# CCM_0020_two_channel_translator.net
KiCad netlist of a schematic drawn in EAGLE
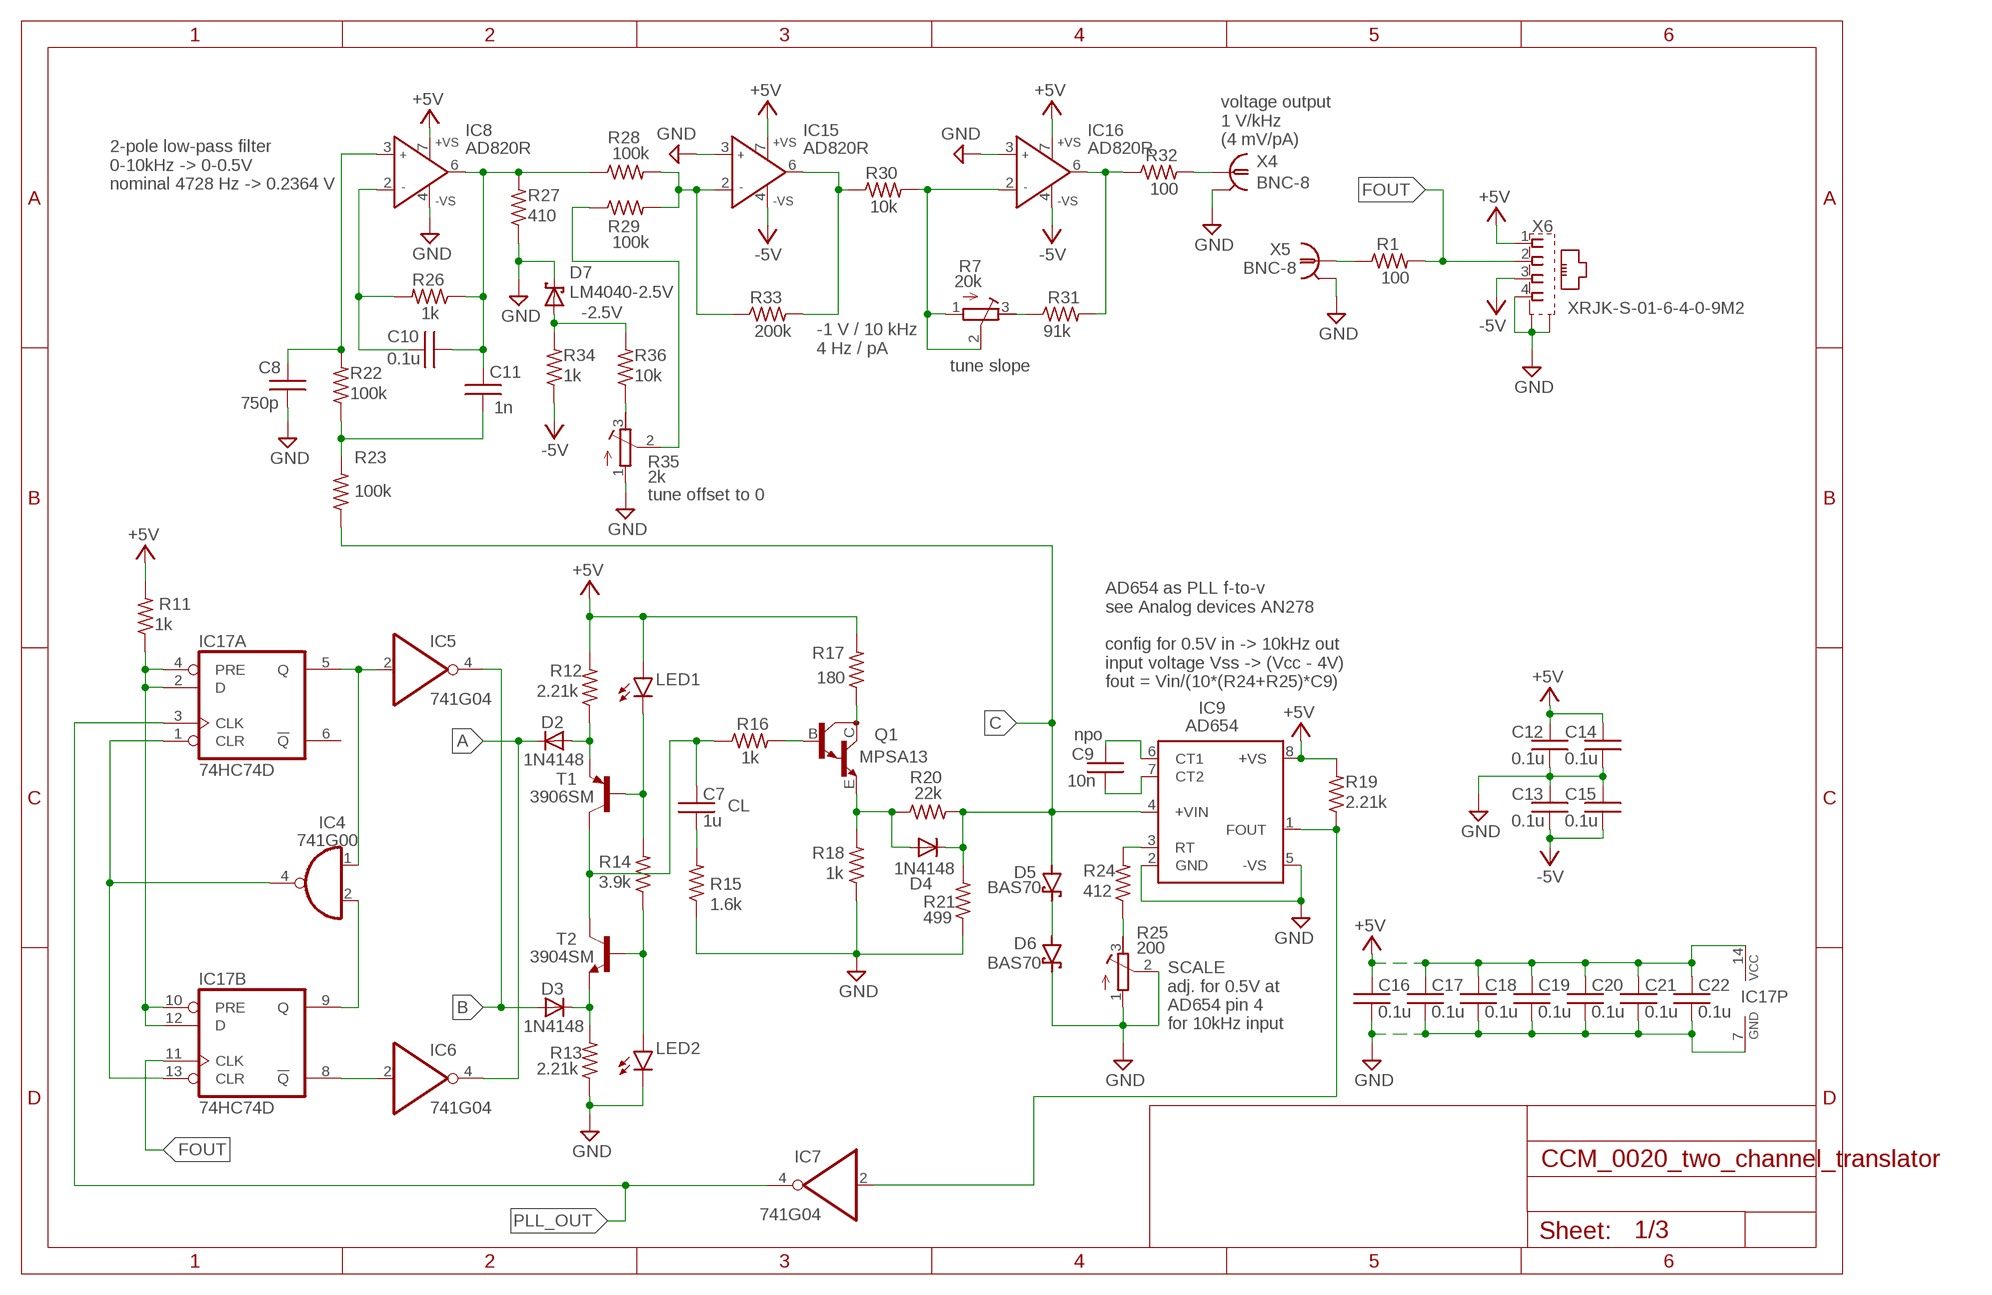
[diagram p0: schematic, sheet 1]
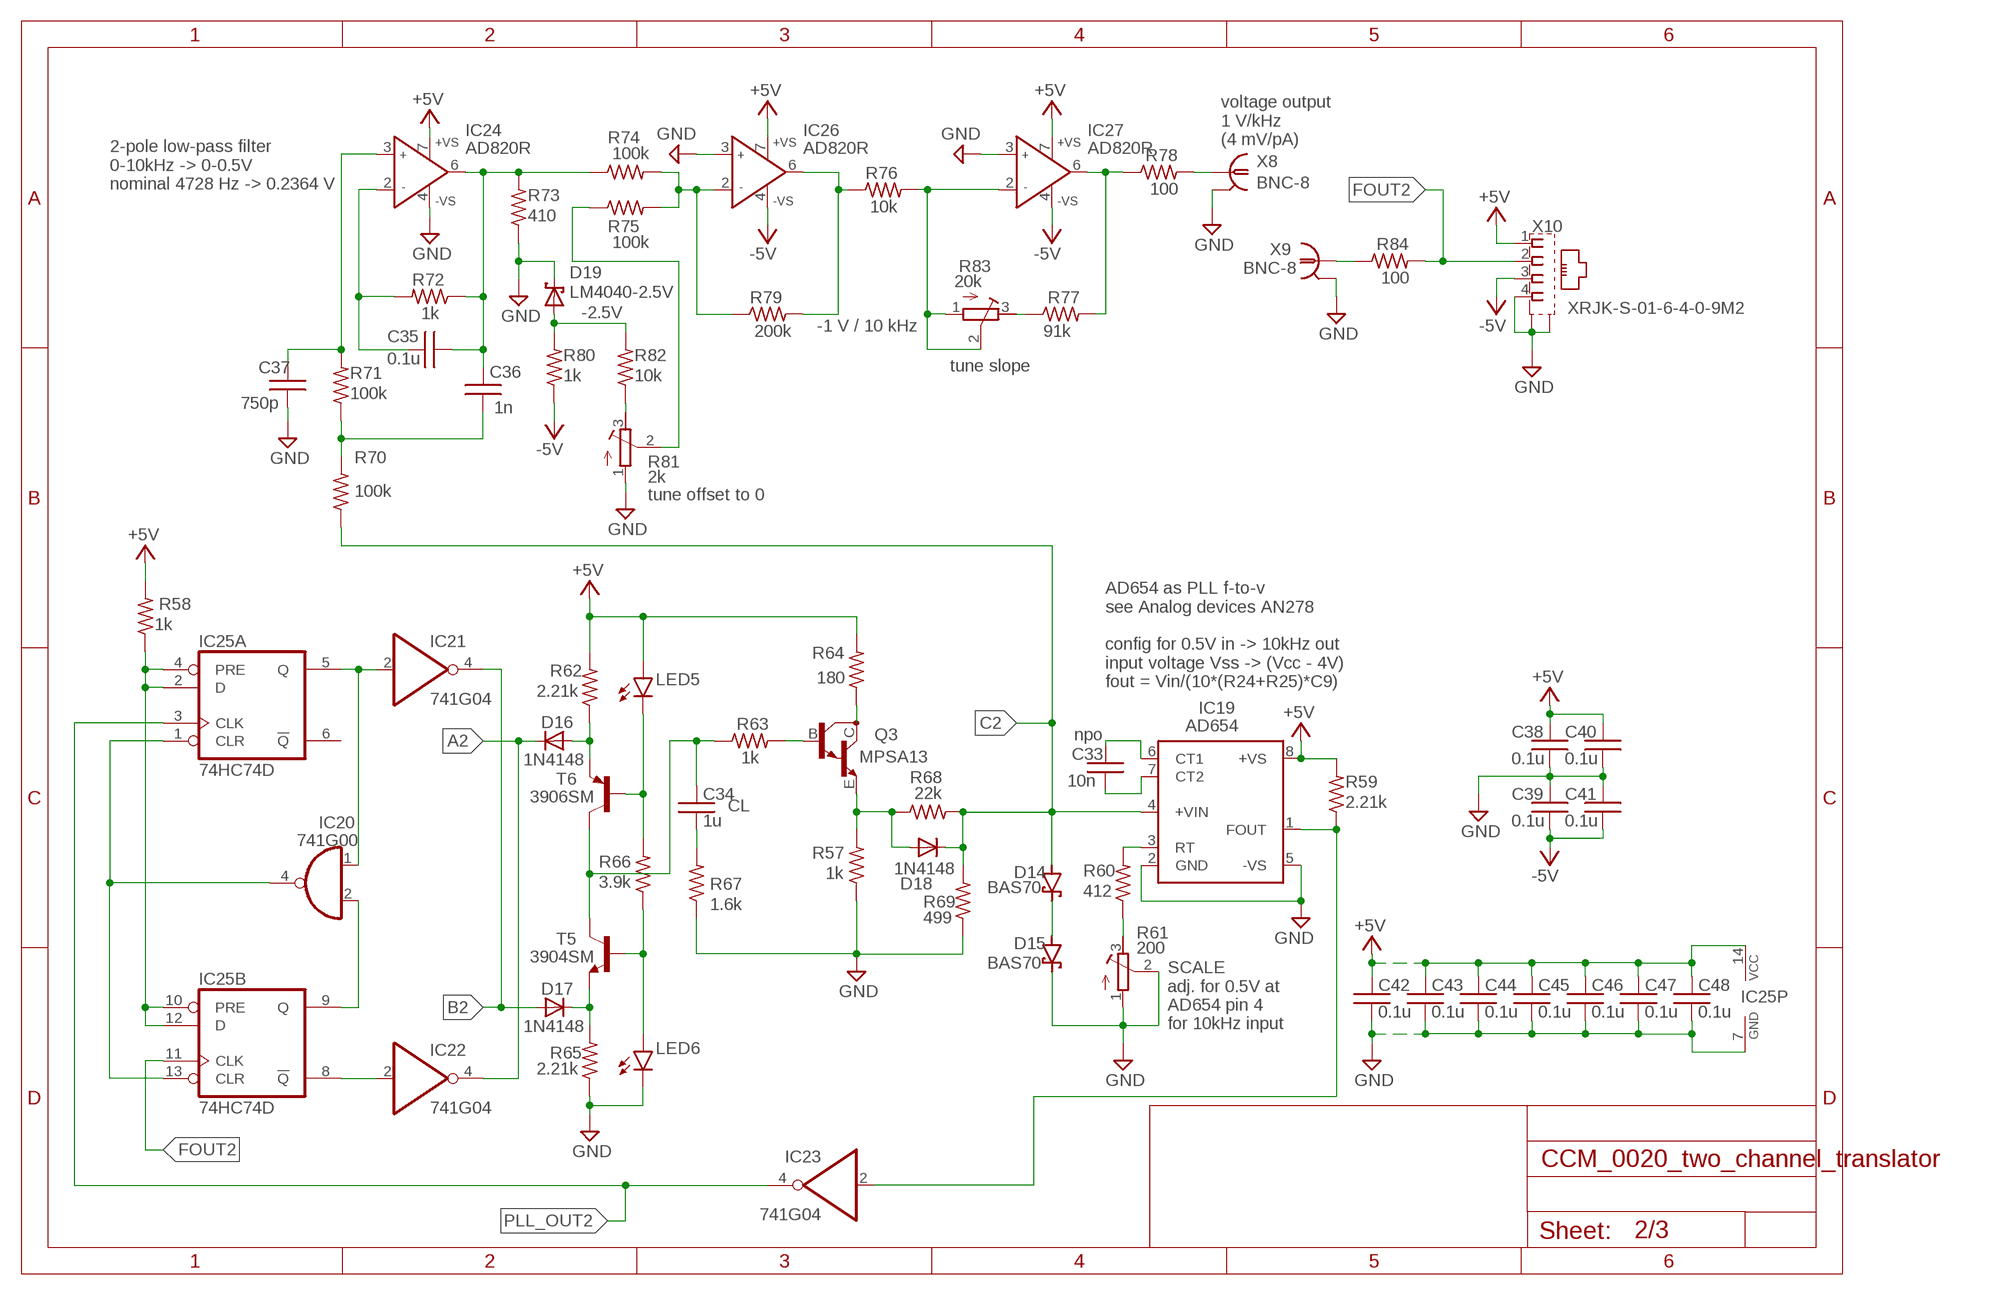
[diagram p1: schematic, sheet 2]
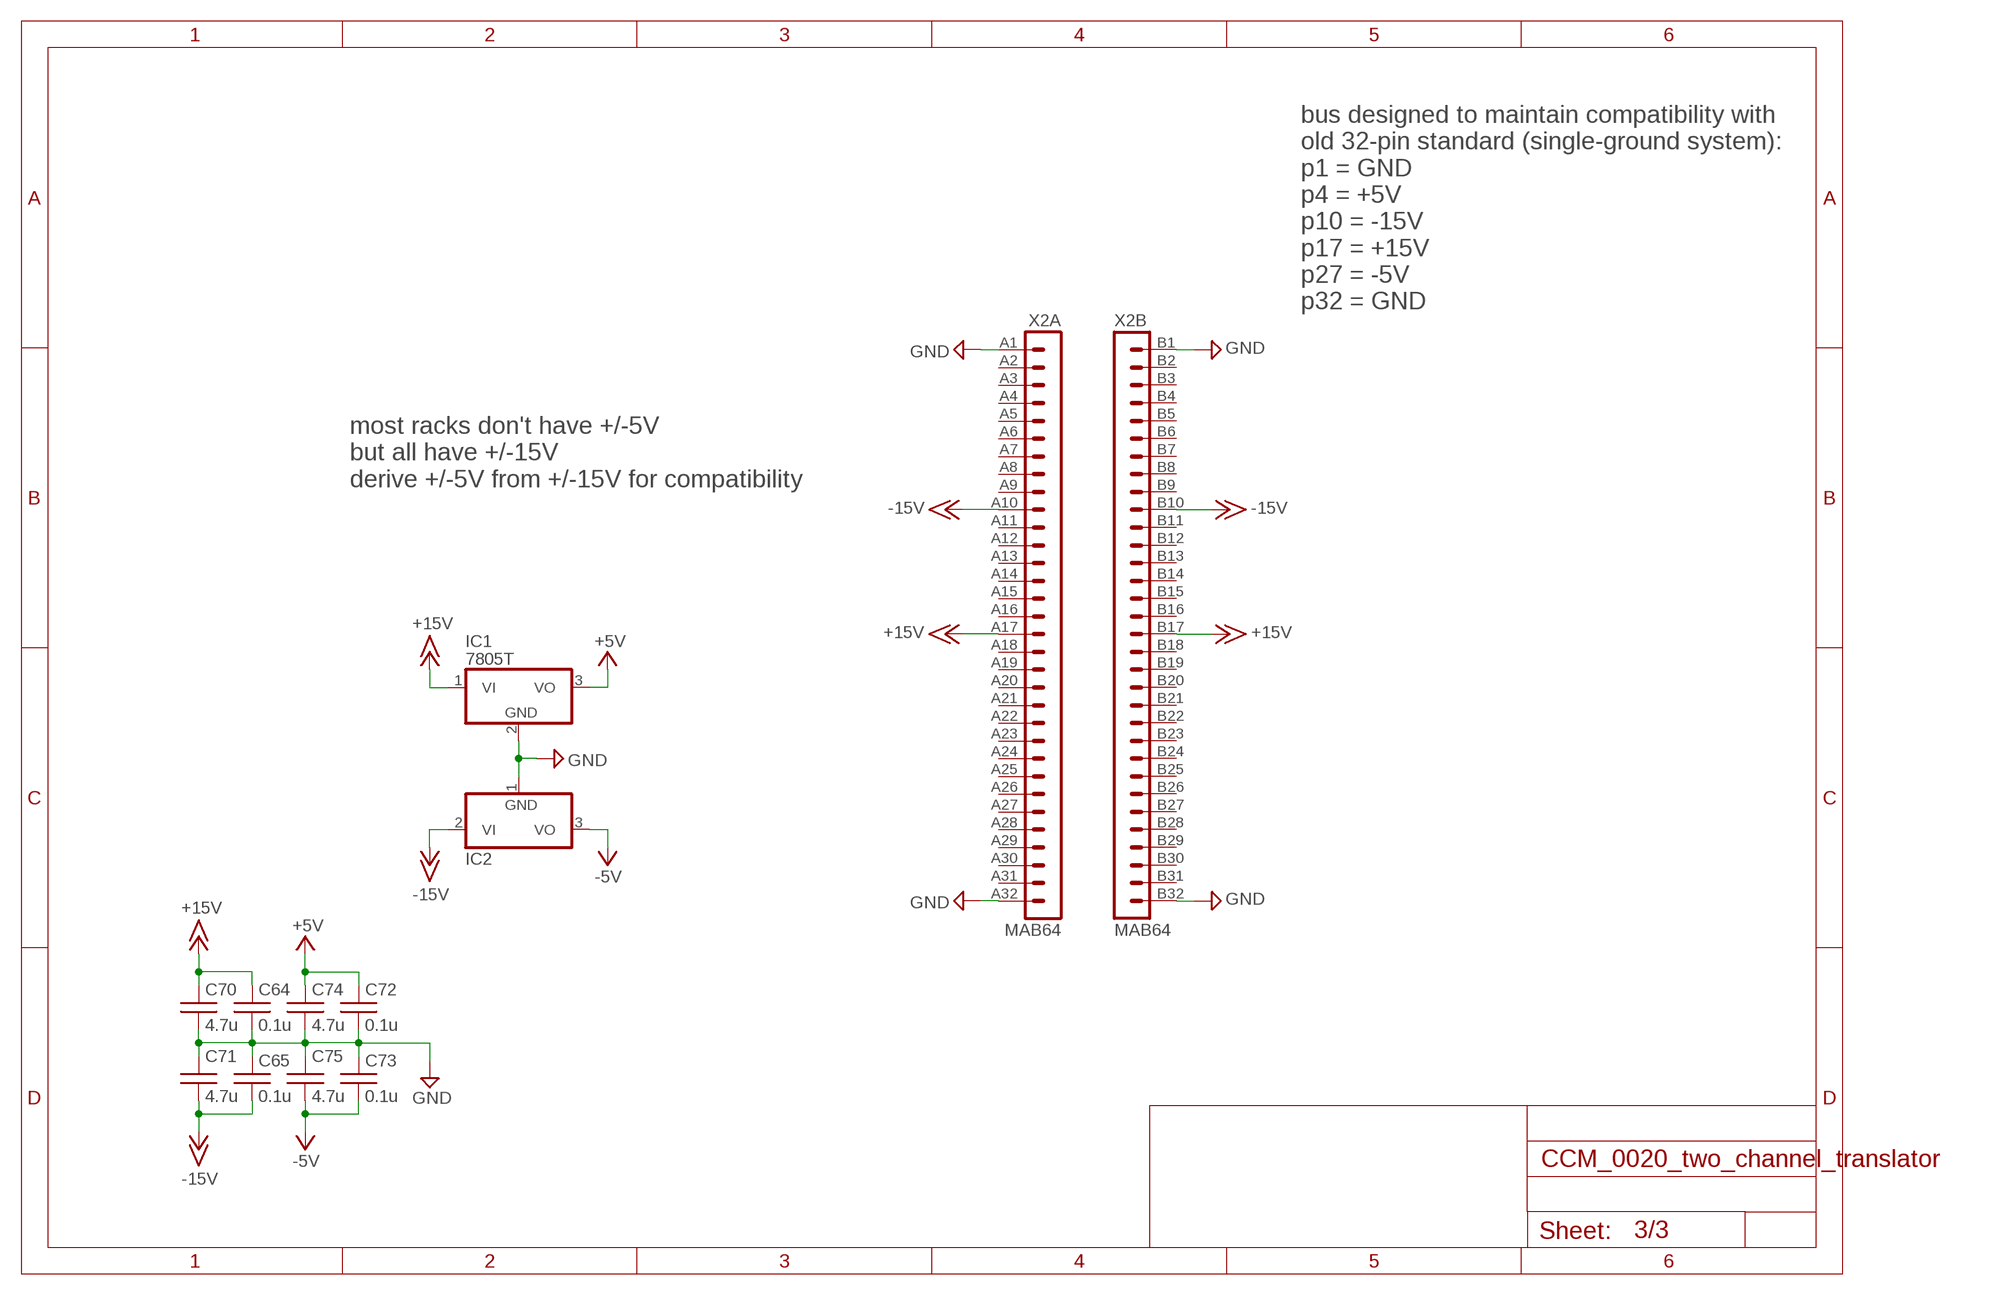
[diagram p2: schematic, sheet 3]

(export (version "E")
  (design (tool "Eeschema 10.0.6"))
  (components
    (comp (ref "C64")
      (value "0.1u")
      (footprint "eagle-import:0603")
      (libsource (lib "eagle-import") (part "C0603"))
    )
    (comp (ref "C65")
      (value "0.1u")
      (footprint "eagle-import:0603")
      (libsource (lib "eagle-import") (part "C0603"))
    )
    (comp (ref "C70")
      (value "4.7u")
      (footprint "eagle-import:0603")
      (libsource (lib "eagle-import") (part "C0603"))
    )
    (comp (ref "C71")
      (value "4.7u")
      (footprint "eagle-import:0603")
      (libsource (lib "eagle-import") (part "C0603"))
    )
    (comp (ref "C72")
      (value "0.1u")
      (footprint "eagle-import:0603")
      (libsource (lib "eagle-import") (part "C0603"))
    )
    (comp (ref "C73")
      (value "0.1u")
      (footprint "eagle-import:0603")
      (libsource (lib "eagle-import") (part "C0603"))
    )
    (comp (ref "C74")
      (value "4.7u")
      (footprint "eagle-import:0603")
      (libsource (lib "eagle-import") (part "C0603"))
    )
    (comp (ref "C75")
      (value "4.7u")
      (footprint "eagle-import:0603")
      (libsource (lib "eagle-import") (part "C0603"))
    )
    (comp (ref "IC1")
      (value "7805T")
      (footprint "eagle-import:TO220H")
      (libsource (lib "eagle-import") (part "78T05"))
    )
    (comp (ref "IC2")
      (value "7905T")
      (footprint "eagle-import:TO220H")
      (libsource (lib "eagle-import") (part "79T05"))
    )
    (comp (ref "X2")
      (value "MAB64")
      (footprint "eagle-import:MAB64")
      (libsource (lib "eagle-import") (part "MAB64"))
    )
    (comp (ref "C7")
      (value "1u")
      (footprint "eagle-import:0603")
      (libsource (lib "eagle-import") (part "C0603"))
    )
    (comp (ref "C8")
      (value "750p")
      (footprint "eagle-import:0603")
      (libsource (lib "eagle-import") (part "C0603"))
    )
    (comp (ref "C9")
      (value "10n")
      (footprint "eagle-import:0603")
      (libsource (lib "eagle-import") (part "C0603"))
    )
    (comp (ref "C10")
      (value "0.1u")
      (footprint "eagle-import:0603")
      (libsource (lib "eagle-import") (part "C0603"))
    )
    (comp (ref "C11")
      (value "1n")
      (footprint "eagle-import:0603")
      (libsource (lib "eagle-import") (part "C0603"))
    )
    (comp (ref "C12")
      (value "0.1u")
      (footprint "eagle-import:0603")
      (libsource (lib "eagle-import") (part "C0603"))
    )
    (comp (ref "C13")
      (value "0.1u")
      (footprint "eagle-import:0603")
      (libsource (lib "eagle-import") (part "C0603"))
    )
    (comp (ref "C14")
      (value "0.1u")
      (footprint "eagle-import:0603")
      (libsource (lib "eagle-import") (part "C0603"))
    )
    (comp (ref "C15")
      (value "0.1u")
      (footprint "eagle-import:0603")
      (libsource (lib "eagle-import") (part "C0603"))
    )
    (comp (ref "C16")
      (value "0.1u")
      (footprint "eagle-import:0603")
      (libsource (lib "eagle-import") (part "C0603"))
    )
    (comp (ref "C17")
      (value "0.1u")
      (footprint "eagle-import:0603")
      (libsource (lib "eagle-import") (part "C0603"))
    )
    (comp (ref "C18")
      (value "0.1u")
      (footprint "eagle-import:0603")
      (libsource (lib "eagle-import") (part "C0603"))
    )
    (comp (ref "C19")
      (value "0.1u")
      (footprint "eagle-import:0603")
      (libsource (lib "eagle-import") (part "C0603"))
    )
    (comp (ref "C20")
      (value "0.1u")
      (footprint "eagle-import:0603")
      (libsource (lib "eagle-import") (part "C0603"))
    )
    (comp (ref "C21")
      (value "0.1u")
      (footprint "eagle-import:0603")
      (libsource (lib "eagle-import") (part "C0603"))
    )
    (comp (ref "C22")
      (value "0.1u")
      (footprint "eagle-import:0603")
      (libsource (lib "eagle-import") (part "C0603"))
    )
    (comp (ref "D2")
      (value "1N4148")
      (footprint "eagle-import:SOD323_ST")
      (libsource (lib "eagle-import") (part "1N4148"))
    )
    (comp (ref "D3")
      (value "1N4148")
      (footprint "eagle-import:SOD323_ST")
      (libsource (lib "eagle-import") (part "1N4148"))
    )
    (comp (ref "D4")
      (value "1N4148")
      (footprint "eagle-import:SOD323_ST")
      (libsource (lib "eagle-import") (part "1N4148"))
    )
    (comp (ref "D5")
      (value "BAS70")
      (footprint "eagle-import:SOT23")
      (libsource (lib "eagle-import") (part "BAS70"))
    )
    (comp (ref "D6")
      (value "BAS70")
      (footprint "eagle-import:SOT23")
      (libsource (lib "eagle-import") (part "BAS70"))
    )
    (comp (ref "D7")
      (value "LM4040-2.5V")
      (footprint "eagle-import:SOT23")
      (libsource (lib "eagle-import") (part "LM4040"))
    )
    (comp (ref "IC4")
      (value "741G00")
      (footprint "eagle-import:SOT23-5")
      (libsource (lib "eagle-import") (part "741G00DBVAHC"))
    )
    (comp (ref "IC5")
      (value "741G04")
      (footprint "eagle-import:SOT23-5")
      (libsource (lib "eagle-import") (part "741G04DBVAHC"))
    )
    (comp (ref "IC6")
      (value "741G04")
      (footprint "eagle-import:SOT23-5")
      (libsource (lib "eagle-import") (part "741G04DBVAHC"))
    )
    (comp (ref "IC7")
      (value "741G04")
      (footprint "eagle-import:SOT23-5")
      (libsource (lib "eagle-import") (part "741G04DBVAHC"))
    )
    (comp (ref "IC8")
      (value "AD820R")
      (footprint "eagle-import:SO8")
      (libsource (lib "eagle-import") (part "AD820R"))
    )
    (comp (ref "IC9")
      (value "AD654")
      (footprint "eagle-import:SO08")
      (libsource (lib "eagle-import") (part "AD654"))
    )
    (comp (ref "IC15")
      (value "AD820R")
      (footprint "eagle-import:SO8")
      (libsource (lib "eagle-import") (part "AD820R"))
    )
    (comp (ref "IC16")
      (value "AD820R")
      (footprint "eagle-import:SO8")
      (libsource (lib "eagle-import") (part "AD820R"))
    )
    (comp (ref "IC17")
      (value "74HC74D")
      (footprint "eagle-import:SO14")
      (libsource (lib "eagle-import") (part "7474DHC"))
    )
    (comp (ref "LED1")
      (value "LEDCHIP-LED0603")
      (footprint "eagle-import:CHIP-LED0603")
      (libsource (lib "eagle-import") (part "LEDCHIP-LED0603"))
    )
    (comp (ref "LED2")
      (value "LEDCHIP-LED0603")
      (footprint "eagle-import:CHIP-LED0603")
      (libsource (lib "eagle-import") (part "LEDCHIP-LED0603"))
    )
    (comp (ref "Q1")
      (value "MPSA13")
      (footprint "eagle-import:SOT23-BEC")
      (libsource (lib "eagle-import") (part "MMBTA13LT1"))
    )
    (comp (ref "R1")
      (value "100")
      (footprint "eagle-import:0603")
      (libsource (lib "eagle-import") (part "R0603"))
    )
    (comp (ref "R7")
      (value "20k")
      (footprint "eagle-import:RTRIM64Y")
      (libsource (lib "eagle-import") (part "R-TRIMM64Y"))
    )
    (comp (ref "R11")
      (value "1k")
      (footprint "eagle-import:0603")
      (libsource (lib "eagle-import") (part "R0603"))
    )
    (comp (ref "R12")
      (value "2.21k")
      (footprint "eagle-import:0603")
      (libsource (lib "eagle-import") (part "R0603"))
    )
    (comp (ref "R13")
      (value "2.21k")
      (footprint "eagle-import:0603")
      (libsource (lib "eagle-import") (part "R0603"))
    )
    (comp (ref "R14")
      (value "3.9k")
      (footprint "eagle-import:0603")
      (libsource (lib "eagle-import") (part "R0603"))
    )
    (comp (ref "R15")
      (value "1.6k")
      (footprint "eagle-import:0603")
      (libsource (lib "eagle-import") (part "R0603"))
    )
    (comp (ref "R16")
      (value "1k")
      (footprint "eagle-import:0603")
      (libsource (lib "eagle-import") (part "R0603"))
    )
    (comp (ref "R17")
      (value "180")
      (footprint "eagle-import:0603")
      (libsource (lib "eagle-import") (part "R0603"))
    )
    (comp (ref "R18")
      (value "1k")
      (footprint "eagle-import:0603")
      (libsource (lib "eagle-import") (part "R0603"))
    )
    (comp (ref "R19")
      (value "2.21k")
      (footprint "eagle-import:0603")
      (libsource (lib "eagle-import") (part "R0603"))
    )
    (comp (ref "R20")
      (value "22k")
      (footprint "eagle-import:0603")
      (libsource (lib "eagle-import") (part "R0603"))
    )
    (comp (ref "R21")
      (value "499")
      (footprint "eagle-import:0603")
      (libsource (lib "eagle-import") (part "R0603"))
    )
    (comp (ref "R22")
      (value "100k")
      (footprint "eagle-import:0603")
      (libsource (lib "eagle-import") (part "R0603"))
    )
    (comp (ref "R23")
      (value "100k")
      (footprint "eagle-import:0603")
      (libsource (lib "eagle-import") (part "R0603"))
    )
    (comp (ref "R24")
      (value "412")
      (footprint "eagle-import:0603")
      (libsource (lib "eagle-import") (part "R0603"))
    )
    (comp (ref "R25")
      (value "200")
      (footprint "eagle-import:RTRIM64Y")
      (libsource (lib "eagle-import") (part "R-TRIMM64Y"))
    )
    (comp (ref "R26")
      (value "1k")
      (footprint "eagle-import:0603")
      (libsource (lib "eagle-import") (part "R0603"))
    )
    (comp (ref "R27")
      (value "410")
      (footprint "eagle-import:0603")
      (libsource (lib "eagle-import") (part "R0603"))
    )
    (comp (ref "R28")
      (value "100k")
      (footprint "eagle-import:0603")
      (libsource (lib "eagle-import") (part "R0603"))
    )
    (comp (ref "R29")
      (value "100k")
      (footprint "eagle-import:0603")
      (libsource (lib "eagle-import") (part "R0603"))
    )
    (comp (ref "R30")
      (value "10k")
      (footprint "eagle-import:0603")
      (libsource (lib "eagle-import") (part "R0603"))
    )
    (comp (ref "R31")
      (value "91k")
      (footprint "eagle-import:0603")
      (libsource (lib "eagle-import") (part "R0603"))
    )
    (comp (ref "R32")
      (value "100")
      (footprint "eagle-import:0603")
      (libsource (lib "eagle-import") (part "R0603"))
    )
    (comp (ref "R33")
      (value "200k")
      (footprint "eagle-import:0603")
      (libsource (lib "eagle-import") (part "R0603"))
    )
    (comp (ref "R34")
      (value "1k")
      (footprint "eagle-import:0603")
      (libsource (lib "eagle-import") (part "R0603"))
    )
    (comp (ref "R35")
      (value "2k")
      (footprint "eagle-import:RTRIM64Y")
      (libsource (lib "eagle-import") (part "R-TRIMM64Y"))
    )
    (comp (ref "R36")
      (value "10k")
      (footprint "eagle-import:0603")
      (libsource (lib "eagle-import") (part "R0603"))
    )
    (comp (ref "T1")
      (value "3906SM")
      (footprint "eagle-import:SOT23-BEC")
      (libsource (lib "eagle-import") (part "-PNP-SOT23-BECMMBT3906LT1"))
    )
    (comp (ref "T2")
      (value "3904SM")
      (footprint "eagle-import:SOT23")
      (libsource (lib "eagle-import") (part "3904SM"))
    )
    (comp (ref "X4")
      (value "BNC-8")
      (footprint "eagle-import:BNC_RA")
      (libsource (lib "eagle-import") (part "BNC-8"))
    )
    (comp (ref "X5")
      (value "BNC-8")
      (footprint "eagle-import:BNC_RA")
      (libsource (lib "eagle-import") (part "BNC-8"))
    )
    (comp (ref "X6")
      (value "XRJK-S-01-6-4-0-9M2")
      (footprint "eagle-import:XRJK-S-01-6-4-0-9M2")
      (libsource (lib "eagle-import") (part "XRJK4-0-9M2-S-01-6-"))
    )
    (comp (ref "C33")
      (value "10n")
      (footprint "eagle-import:0603")
      (libsource (lib "eagle-import") (part "C0603"))
    )
    (comp (ref "C34")
      (value "1u")
      (footprint "eagle-import:0603")
      (libsource (lib "eagle-import") (part "C0603"))
    )
    (comp (ref "C35")
      (value "0.1u")
      (footprint "eagle-import:0603")
      (libsource (lib "eagle-import") (part "C0603"))
    )
    (comp (ref "C36")
      (value "1n")
      (footprint "eagle-import:0603")
      (libsource (lib "eagle-import") (part "C0603"))
    )
    (comp (ref "C37")
      (value "750p")
      (footprint "eagle-import:0603")
      (libsource (lib "eagle-import") (part "C0603"))
    )
    (comp (ref "C38")
      (value "0.1u")
      (footprint "eagle-import:0603")
      (libsource (lib "eagle-import") (part "C0603"))
    )
    (comp (ref "C39")
      (value "0.1u")
      (footprint "eagle-import:0603")
      (libsource (lib "eagle-import") (part "C0603"))
    )
    (comp (ref "C40")
      (value "0.1u")
      (footprint "eagle-import:0603")
      (libsource (lib "eagle-import") (part "C0603"))
    )
    (comp (ref "C41")
      (value "0.1u")
      (footprint "eagle-import:0603")
      (libsource (lib "eagle-import") (part "C0603"))
    )
    (comp (ref "C42")
      (value "0.1u")
      (footprint "eagle-import:0603")
      (libsource (lib "eagle-import") (part "C0603"))
    )
    (comp (ref "C43")
      (value "0.1u")
      (footprint "eagle-import:0603")
      (libsource (lib "eagle-import") (part "C0603"))
    )
    (comp (ref "C44")
      (value "0.1u")
      (footprint "eagle-import:0603")
      (libsource (lib "eagle-import") (part "C0603"))
    )
    (comp (ref "C45")
      (value "0.1u")
      (footprint "eagle-import:0603")
      (libsource (lib "eagle-import") (part "C0603"))
    )
    (comp (ref "C46")
      (value "0.1u")
      (footprint "eagle-import:0603")
      (libsource (lib "eagle-import") (part "C0603"))
    )
    (comp (ref "C47")
      (value "0.1u")
      (footprint "eagle-import:0603")
      (libsource (lib "eagle-import") (part "C0603"))
    )
    (comp (ref "C48")
      (value "0.1u")
      (footprint "eagle-import:0603")
      (libsource (lib "eagle-import") (part "C0603"))
    )
    (comp (ref "D14")
      (value "BAS70")
      (footprint "eagle-import:SOT23")
      (libsource (lib "eagle-import") (part "BAS70"))
    )
    (comp (ref "D15")
      (value "BAS70")
      (footprint "eagle-import:SOT23")
      (libsource (lib "eagle-import") (part "BAS70"))
    )
    (comp (ref "D16")
      (value "1N4148")
      (footprint "eagle-import:SOD323_ST")
      (libsource (lib "eagle-import") (part "1N4148"))
    )
    (comp (ref "D17")
      (value "1N4148")
      (footprint "eagle-import:SOD323_ST")
      (libsource (lib "eagle-import") (part "1N4148"))
    )
    (comp (ref "D18")
      (value "1N4148")
      (footprint "eagle-import:SOD323_ST")
      (libsource (lib "eagle-import") (part "1N4148"))
    )
    (comp (ref "D19")
      (value "LM4040-2.5V")
      (footprint "eagle-import:SOT23")
      (libsource (lib "eagle-import") (part "LM4040"))
    )
    (comp (ref "IC19")
      (value "AD654")
      (footprint "eagle-import:SO08")
      (libsource (lib "eagle-import") (part "AD654"))
    )
    (comp (ref "IC20")
      (value "741G00")
      (footprint "eagle-import:SOT23-5")
      (libsource (lib "eagle-import") (part "741G00DBVAHC"))
    )
    (comp (ref "IC21")
      (value "741G04")
      (footprint "eagle-import:SOT23-5")
      (libsource (lib "eagle-import") (part "741G04DBVAHC"))
    )
    (comp (ref "IC22")
      (value "741G04")
      (footprint "eagle-import:SOT23-5")
      (libsource (lib "eagle-import") (part "741G04DBVAHC"))
    )
    (comp (ref "IC23")
      (value "741G04")
      (footprint "eagle-import:SOT23-5")
      (libsource (lib "eagle-import") (part "741G04DBVAHC"))
    )
    (comp (ref "IC24")
      (value "AD820R")
      (footprint "eagle-import:SO8")
      (libsource (lib "eagle-import") (part "AD820R"))
    )
    (comp (ref "IC25")
      (value "74HC74D")
      (footprint "eagle-import:SO14")
      (libsource (lib "eagle-import") (part "7474DHC"))
    )
    (comp (ref "IC26")
      (value "AD820R")
      (footprint "eagle-import:SO8")
      (libsource (lib "eagle-import") (part "AD820R"))
    )
    (comp (ref "IC27")
      (value "AD820R")
      (footprint "eagle-import:SO8")
      (libsource (lib "eagle-import") (part "AD820R"))
    )
    (comp (ref "LED5")
      (value "LEDCHIP-LED0603")
      (footprint "eagle-import:CHIP-LED0603")
      (libsource (lib "eagle-import") (part "LEDCHIP-LED0603"))
    )
    (comp (ref "LED6")
      (value "LEDCHIP-LED0603")
      (footprint "eagle-import:CHIP-LED0603")
      (libsource (lib "eagle-import") (part "LEDCHIP-LED0603"))
    )
    (comp (ref "Q3")
      (value "MPSA13")
      (footprint "eagle-import:SOT23-BEC")
      (libsource (lib "eagle-import") (part "MMBTA13LT1"))
    )
    (comp (ref "R57")
      (value "1k")
      (footprint "eagle-import:0603")
      (libsource (lib "eagle-import") (part "R0603"))
    )
    (comp (ref "R58")
      (value "1k")
      (footprint "eagle-import:0603")
      (libsource (lib "eagle-import") (part "R0603"))
    )
    (comp (ref "R59")
      (value "2.21k")
      (footprint "eagle-import:0603")
      (libsource (lib "eagle-import") (part "R0603"))
    )
    (comp (ref "R60")
      (value "412")
      (footprint "eagle-import:0603")
      (libsource (lib "eagle-import") (part "R0603"))
    )
    (comp (ref "R61")
      (value "200")
      (footprint "eagle-import:RTRIM64Y")
      (libsource (lib "eagle-import") (part "R-TRIMM64Y"))
    )
    (comp (ref "R62")
      (value "2.21k")
      (footprint "eagle-import:0603")
      (libsource (lib "eagle-import") (part "R0603"))
    )
    (comp (ref "R63")
      (value "1k")
      (footprint "eagle-import:0603")
      (libsource (lib "eagle-import") (part "R0603"))
    )
    (comp (ref "R64")
      (value "180")
      (footprint "eagle-import:0603")
      (libsource (lib "eagle-import") (part "R0603"))
    )
    (comp (ref "R65")
      (value "2.21k")
      (footprint "eagle-import:0603")
      (libsource (lib "eagle-import") (part "R0603"))
    )
    (comp (ref "R66")
      (value "3.9k")
      (footprint "eagle-import:0603")
      (libsource (lib "eagle-import") (part "R0603"))
    )
    (comp (ref "R67")
      (value "1.6k")
      (footprint "eagle-import:0603")
      (libsource (lib "eagle-import") (part "R0603"))
    )
    (comp (ref "R68")
      (value "22k")
      (footprint "eagle-import:0603")
      (libsource (lib "eagle-import") (part "R0603"))
    )
    (comp (ref "R69")
      (value "499")
      (footprint "eagle-import:0603")
      (libsource (lib "eagle-import") (part "R0603"))
    )
    (comp (ref "R70")
      (value "100k")
      (footprint "eagle-import:0603")
      (libsource (lib "eagle-import") (part "R0603"))
    )
    (comp (ref "R71")
      (value "100k")
      (footprint "eagle-import:0603")
      (libsource (lib "eagle-import") (part "R0603"))
    )
    (comp (ref "R72")
      (value "1k")
      (footprint "eagle-import:0603")
      (libsource (lib "eagle-import") (part "R0603"))
    )
    (comp (ref "R73")
      (value "410")
      (footprint "eagle-import:0603")
      (libsource (lib "eagle-import") (part "R0603"))
    )
    (comp (ref "R74")
      (value "100k")
      (footprint "eagle-import:0603")
      (libsource (lib "eagle-import") (part "R0603"))
    )
    (comp (ref "R75")
      (value "100k")
      (footprint "eagle-import:0603")
      (libsource (lib "eagle-import") (part "R0603"))
    )
    (comp (ref "R76")
      (value "10k")
      (footprint "eagle-import:0603")
      (libsource (lib "eagle-import") (part "R0603"))
    )
    (comp (ref "R77")
      (value "91k")
      (footprint "eagle-import:0603")
      (libsource (lib "eagle-import") (part "R0603"))
    )
    (comp (ref "R78")
      (value "100")
      (footprint "eagle-import:0603")
      (libsource (lib "eagle-import") (part "R0603"))
    )
    (comp (ref "R79")
      (value "200k")
      (footprint "eagle-import:0603")
      (libsource (lib "eagle-import") (part "R0603"))
    )
    (comp (ref "R80")
      (value "1k")
      (footprint "eagle-import:0603")
      (libsource (lib "eagle-import") (part "R0603"))
    )
    (comp (ref "R81")
      (value "2k")
      (footprint "eagle-import:RTRIM64Y")
      (libsource (lib "eagle-import") (part "R-TRIMM64Y"))
    )
    (comp (ref "R82")
      (value "10k")
      (footprint "eagle-import:0603")
      (libsource (lib "eagle-import") (part "R0603"))
    )
    (comp (ref "R83")
      (value "20k")
      (footprint "eagle-import:RTRIM64Y")
      (libsource (lib "eagle-import") (part "R-TRIMM64Y"))
    )
    (comp (ref "R84")
      (value "100")
      (footprint "eagle-import:0603")
      (libsource (lib "eagle-import") (part "R0603"))
    )
    (comp (ref "T5")
      (value "3904SM")
      (footprint "eagle-import:SOT23")
      (libsource (lib "eagle-import") (part "3904SM"))
    )
    (comp (ref "T6")
      (value "3906SM")
      (footprint "eagle-import:SOT23-BEC")
      (libsource (lib "eagle-import") (part "-PNP-SOT23-BECMMBT3906LT1"))
    )
    (comp (ref "X8")
      (value "BNC-8")
      (footprint "eagle-import:BNC_RA")
      (libsource (lib "eagle-import") (part "BNC-8"))
    )
    (comp (ref "X9")
      (value "BNC-8")
      (footprint "eagle-import:BNC_RA")
      (libsource (lib "eagle-import") (part "BNC-8"))
    )
    (comp (ref "X10")
      (value "XRJK-S-01-6-4-0-9M2")
      (footprint "eagle-import:XRJK-S-01-6-4-0-9M2")
      (libsource (lib "eagle-import") (part "XRJK4-0-9M2-S-01-6-"))
    )
  )
  (nets
    (net (code "1") (name "+5V") (class "Default")
      (node (ref "C12") (pin "2") (pinfunction "2_2") (pintype "passive"))
      (node (ref "C14") (pin "2") (pinfunction "2_2") (pintype "passive"))
      (node (ref "C16") (pin "1") (pinfunction "1_1") (pintype "passive"))
      (node (ref "C17") (pin "1") (pinfunction "1_1") (pintype "passive"))
      (node (ref "C18") (pin "1") (pinfunction "1_1") (pintype "passive"))
      (node (ref "C19") (pin "1") (pinfunction "1_1") (pintype "passive"))
      (node (ref "C20") (pin "1") (pinfunction "1_1") (pintype "passive"))
      (node (ref "C21") (pin "1") (pinfunction "1_1") (pintype "passive"))
      (node (ref "C22") (pin "1") (pinfunction "1_1") (pintype "passive"))
      (node (ref "C38") (pin "2") (pinfunction "2_2") (pintype "passive"))
      (node (ref "C40") (pin "2") (pinfunction "2_2") (pintype "passive"))
      (node (ref "C42") (pin "1") (pinfunction "1_1") (pintype "passive"))
      (node (ref "C43") (pin "1") (pinfunction "1_1") (pintype "passive"))
      (node (ref "C44") (pin "1") (pinfunction "1_1") (pintype "passive"))
      (node (ref "C45") (pin "1") (pinfunction "1_1") (pintype "passive"))
      (node (ref "C46") (pin "1") (pinfunction "1_1") (pintype "passive"))
      (node (ref "C47") (pin "1") (pinfunction "1_1") (pintype "passive"))
      (node (ref "C48") (pin "1") (pinfunction "1_1") (pintype "passive"))
      (node (ref "C72") (pin "1") (pinfunction "1_1") (pintype "passive"))
      (node (ref "C74") (pin "1") (pinfunction "1_1") (pintype "passive"))
      (node (ref "IC1") (pin "3") (pinfunction "VO_3") (pintype "passive"))
      (node (ref "IC15") (pin "7") (pinfunction "+VS_7") (pintype "input"))
      (node (ref "IC16") (pin "7") (pinfunction "+VS_7") (pintype "input"))
      (node (ref "IC17") (pin "14") (pinfunction "VCC_14") (pintype "power_in"))
      (node (ref "IC19") (pin "8") (pinfunction "+VS_8") (pintype "power_in"))
      (node (ref "IC24") (pin "7") (pinfunction "+VS_7") (pintype "input"))
      (node (ref "IC25") (pin "14") (pinfunction "VCC_14") (pintype "power_in"))
      (node (ref "IC26") (pin "7") (pinfunction "+VS_7") (pintype "input"))
      (node (ref "IC27") (pin "7") (pinfunction "+VS_7") (pintype "input"))
      (node (ref "IC8") (pin "7") (pinfunction "+VS_7") (pintype "input"))
      (node (ref "IC9") (pin "8") (pinfunction "+VS_8") (pintype "power_in"))
      (node (ref "LED1") (pin "A") (pinfunction "A_A") (pintype "passive"))
      (node (ref "LED5") (pin "A") (pinfunction "A_A") (pintype "passive"))
      (node (ref "R11") (pin "2") (pinfunction "2_2") (pintype "passive"))
      (node (ref "R12") (pin "2") (pinfunction "2_2") (pintype "passive"))
      (node (ref "R17") (pin "2") (pinfunction "2_2") (pintype "passive"))
      (node (ref "R19") (pin "2") (pinfunction "2_2") (pintype "passive"))
      (node (ref "R58") (pin "2") (pinfunction "2_2") (pintype "passive"))
      (node (ref "R59") (pin "2") (pinfunction "2_2") (pintype "passive"))
      (node (ref "R62") (pin "2") (pinfunction "2_2") (pintype "passive"))
      (node (ref "R64") (pin "2") (pinfunction "2_2") (pintype "passive"))
      (node (ref "X10") (pin "1") (pinfunction "1_1") (pintype "passive"))
      (node (ref "X6") (pin "1") (pinfunction "1_1") (pintype "passive"))
    )
    (net (code "2") (name "+15V") (class "Default")
      (node (ref "C64") (pin "1") (pinfunction "1_1") (pintype "passive"))
      (node (ref "C70") (pin "1") (pinfunction "1_1") (pintype "passive"))
      (node (ref "IC1") (pin "1") (pinfunction "VI_1") (pintype "input"))
      (node (ref "X2") (pin "A17") (pinfunction "17_A17") (pintype "passive"))
      (node (ref "X2") (pin "B17") (pinfunction "17_B17") (pintype "passive"))
    )
    (net (code "3") (name "-5V") (class "Default")
      (node (ref "C13") (pin "1") (pinfunction "1_1") (pintype "passive"))
      (node (ref "C15") (pin "1") (pinfunction "1_1") (pintype "passive"))
      (node (ref "C39") (pin "1") (pinfunction "1_1") (pintype "passive"))
      (node (ref "C41") (pin "1") (pinfunction "1_1") (pintype "passive"))
      (node (ref "C73") (pin "2") (pinfunction "2_2") (pintype "passive"))
      (node (ref "C75") (pin "2") (pinfunction "2_2") (pintype "passive"))
      (node (ref "IC15") (pin "4") (pinfunction "-VS_4") (pintype "input"))
      (node (ref "IC16") (pin "4") (pinfunction "-VS_4") (pintype "input"))
      (node (ref "IC2") (pin "3") (pinfunction "VO_3") (pintype "passive"))
      (node (ref "IC26") (pin "4") (pinfunction "-VS_4") (pintype "input"))
      (node (ref "IC27") (pin "4") (pinfunction "-VS_4") (pintype "input"))
      (node (ref "R34") (pin "1") (pinfunction "1_1") (pintype "passive"))
      (node (ref "R80") (pin "1") (pinfunction "1_1") (pintype "passive"))
      (node (ref "X10") (pin "3") (pinfunction "3_3") (pintype "passive"))
      (node (ref "X6") (pin "3") (pinfunction "3_3") (pintype "passive"))
    )
    (net (code "4") (name "-15V") (class "Default")
      (node (ref "C65") (pin "2") (pinfunction "2_2") (pintype "passive"))
      (node (ref "C71") (pin "2") (pinfunction "2_2") (pintype "passive"))
      (node (ref "IC2") (pin "2") (pinfunction "VI_2") (pintype "input"))
      (node (ref "X2") (pin "A10") (pinfunction "10_A10") (pintype "passive"))
      (node (ref "X2") (pin "B10") (pinfunction "10_B10") (pintype "passive"))
    )
    (net (code "5") (name "A") (class "Default")
      (node (ref "D2") (pin "C") (pinfunction "C_C") (pintype "passive"))
      (node (ref "IC6") (pin "4") (pinfunction "O_4") (pintype "output"))
    )
    (net (code "6") (name "A2") (class "Default")
      (node (ref "D16") (pin "C") (pinfunction "C_C") (pintype "passive"))
      (node (ref "IC22") (pin "4") (pinfunction "O_4") (pintype "output"))
    )
    (net (code "7") (name "B") (class "Default")
      (node (ref "D3") (pin "A") (pinfunction "A_A") (pintype "passive"))
      (node (ref "IC5") (pin "4") (pinfunction "O_4") (pintype "output"))
    )
    (net (code "8") (name "B2") (class "Default")
      (node (ref "D17") (pin "A") (pinfunction "A_A") (pintype "passive"))
      (node (ref "IC21") (pin "4") (pinfunction "O_4") (pintype "output"))
    )
    (net (code "9") (name "C") (class "Default")
      (node (ref "D4") (pin "C") (pinfunction "C_C") (pintype "passive"))
      (node (ref "D5") (pin "1") (pinfunction "A_1") (pintype "passive"))
      (node (ref "IC9") (pin "4") (pinfunction "+VIN_4") (pintype "input"))
      (node (ref "R20") (pin "2") (pinfunction "2_2") (pintype "passive"))
      (node (ref "R21") (pin "2") (pinfunction "2_2") (pintype "passive"))
      (node (ref "R23") (pin "1") (pinfunction "1_1") (pintype "passive"))
    )
    (net (code "10") (name "C2") (class "Default")
      (node (ref "D14") (pin "1") (pinfunction "A_1") (pintype "passive"))
      (node (ref "D18") (pin "C") (pinfunction "C_C") (pintype "passive"))
      (node (ref "IC19") (pin "4") (pinfunction "+VIN_4") (pintype "input"))
      (node (ref "R68") (pin "2") (pinfunction "2_2") (pintype "passive"))
      (node (ref "R69") (pin "2") (pinfunction "2_2") (pintype "passive"))
      (node (ref "R70") (pin "1") (pinfunction "1_1") (pintype "passive"))
    )
    (net (code "11") (name "FOUT") (class "Default")
      (node (ref "IC17") (pin "11") (pinfunction "CLK_11") (pintype "input"))
      (node (ref "R1") (pin "2") (pinfunction "2_2") (pintype "passive"))
      (node (ref "X6") (pin "2") (pinfunction "2_2") (pintype "passive"))
    )
    (net (code "12") (name "FOUT2") (class "Default")
      (node (ref "IC25") (pin "11") (pinfunction "CLK_11") (pintype "input"))
      (node (ref "R84") (pin "2") (pinfunction "2_2") (pintype "passive"))
      (node (ref "X10") (pin "2") (pinfunction "2_2") (pintype "passive"))
    )
    (net (code "13") (name "GND") (class "Default")
      (node (ref "C12") (pin "1") (pinfunction "1_1") (pintype "passive"))
      (node (ref "C13") (pin "2") (pinfunction "2_2") (pintype "passive"))
      (node (ref "C14") (pin "1") (pinfunction "1_1") (pintype "passive"))
      (node (ref "C15") (pin "2") (pinfunction "2_2") (pintype "passive"))
      (node (ref "C16") (pin "2") (pinfunction "2_2") (pintype "passive"))
      (node (ref "C17") (pin "2") (pinfunction "2_2") (pintype "passive"))
      (node (ref "C18") (pin "2") (pinfunction "2_2") (pintype "passive"))
      (node (ref "C19") (pin "2") (pinfunction "2_2") (pintype "passive"))
      (node (ref "C20") (pin "2") (pinfunction "2_2") (pintype "passive"))
      (node (ref "C21") (pin "2") (pinfunction "2_2") (pintype "passive"))
      (node (ref "C22") (pin "2") (pinfunction "2_2") (pintype "passive"))
      (node (ref "C37") (pin "1") (pinfunction "1_1") (pintype "passive"))
      (node (ref "C38") (pin "1") (pinfunction "1_1") (pintype "passive"))
      (node (ref "C39") (pin "2") (pinfunction "2_2") (pintype "passive"))
      (node (ref "C40") (pin "1") (pinfunction "1_1") (pintype "passive"))
      (node (ref "C41") (pin "2") (pinfunction "2_2") (pintype "passive"))
      (node (ref "C42") (pin "2") (pinfunction "2_2") (pintype "passive"))
      (node (ref "C43") (pin "2") (pinfunction "2_2") (pintype "passive"))
      (node (ref "C44") (pin "2") (pinfunction "2_2") (pintype "passive"))
      (node (ref "C45") (pin "2") (pinfunction "2_2") (pintype "passive"))
      (node (ref "C46") (pin "2") (pinfunction "2_2") (pintype "passive"))
      (node (ref "C47") (pin "2") (pinfunction "2_2") (pintype "passive"))
      (node (ref "C48") (pin "2") (pinfunction "2_2") (pintype "passive"))
      (node (ref "C64") (pin "2") (pinfunction "2_2") (pintype "passive"))
      (node (ref "C65") (pin "1") (pinfunction "1_1") (pintype "passive"))
      (node (ref "C70") (pin "2") (pinfunction "2_2") (pintype "passive"))
      (node (ref "C71") (pin "1") (pinfunction "1_1") (pintype "passive"))
      (node (ref "C72") (pin "2") (pinfunction "2_2") (pintype "passive"))
      (node (ref "C73") (pin "1") (pinfunction "1_1") (pintype "passive"))
      (node (ref "C74") (pin "2") (pinfunction "2_2") (pintype "passive"))
      (node (ref "C75") (pin "1") (pinfunction "1_1") (pintype "passive"))
      (node (ref "C8") (pin "1") (pinfunction "1_1") (pintype "passive"))
      (node (ref "D15") (pin "3") (pinfunction "C_3") (pintype "passive"))
      (node (ref "D19") (pin "1") (pinfunction "C_1") (pintype "passive"))
      (node (ref "D6") (pin "3") (pinfunction "C_3") (pintype "passive"))
      (node (ref "D7") (pin "1") (pinfunction "C_1") (pintype "passive"))
      (node (ref "IC1") (pin "2") (pinfunction "GND_2") (pintype "passive"))
      (node (ref "IC15") (pin "3") (pinfunction "IN+_3") (pintype "input"))
      (node (ref "IC16") (pin "3") (pinfunction "IN+_3") (pintype "input"))
      (node (ref "IC17") (pin "7") (pinfunction "GND_7") (pintype "power_in"))
      (node (ref "IC19") (pin "2") (pinfunction "GND_2") (pintype "power_in"))
      (node (ref "IC19") (pin "5") (pinfunction "-VS_5") (pintype "power_in"))
      (node (ref "IC2") (pin "1") (pinfunction "GND_1") (pintype "passive"))
      (node (ref "IC24") (pin "4") (pinfunction "-VS_4") (pintype "input"))
      (node (ref "IC25") (pin "7") (pinfunction "GND_7") (pintype "power_in"))
      (node (ref "IC26") (pin "3") (pinfunction "IN+_3") (pintype "input"))
      (node (ref "IC27") (pin "3") (pinfunction "IN+_3") (pintype "input"))
      (node (ref "IC8") (pin "4") (pinfunction "-VS_4") (pintype "input"))
      (node (ref "IC9") (pin "2") (pinfunction "GND_2") (pintype "power_in"))
      (node (ref "IC9") (pin "5") (pinfunction "-VS_5") (pintype "power_in"))
      (node (ref "LED2") (pin "C") (pinfunction "C_C") (pintype "passive"))
      (node (ref "LED6") (pin "C") (pinfunction "C_C") (pintype "passive"))
      (node (ref "R13") (pin "1") (pinfunction "1_1") (pintype "passive"))
      (node (ref "R15") (pin "1") (pinfunction "1_1") (pintype "passive"))
      (node (ref "R18") (pin "1") (pinfunction "1_1") (pintype "passive"))
      (node (ref "R21") (pin "1") (pinfunction "1_1") (pintype "passive"))
      (node (ref "R25") (pin "1") (pinfunction "A_1") (pintype "passive"))
      (node (ref "R25") (pin "2") (pinfunction "S_2") (pintype "passive"))
      (node (ref "R27") (pin "1") (pinfunction "1_1") (pintype "passive"))
      (node (ref "R35") (pin "1") (pinfunction "A_1") (pintype "passive"))
      (node (ref "R57") (pin "1") (pinfunction "1_1") (pintype "passive"))
      (node (ref "R61") (pin "1") (pinfunction "A_1") (pintype "passive"))
      (node (ref "R61") (pin "2") (pinfunction "S_2") (pintype "passive"))
      (node (ref "R65") (pin "1") (pinfunction "1_1") (pintype "passive"))
      (node (ref "R67") (pin "1") (pinfunction "1_1") (pintype "passive"))
      (node (ref "R69") (pin "1") (pinfunction "1_1") (pintype "passive"))
      (node (ref "R73") (pin "1") (pinfunction "1_1") (pintype "passive"))
      (node (ref "R81") (pin "1") (pinfunction "A_1") (pintype "passive"))
      (node (ref "X10") (pin "4") (pinfunction "4_4") (pintype "passive"))
      (node (ref "X10") (pin "S1") (pinfunction "S_S1") (pintype "passive"))
      (node (ref "X10") (pin "S2") (pinfunction "S_S2") (pintype "passive"))
      (node (ref "X2") (pin "A1") (pinfunction "1_A1") (pintype "passive"))
      (node (ref "X2") (pin "A32") (pinfunction "32_A32") (pintype "passive"))
      (node (ref "X2") (pin "B1") (pinfunction "1_B1") (pintype "passive"))
      (node (ref "X2") (pin "B32") (pinfunction "32_B32") (pintype "passive"))
      (node (ref "X4") (pin "2") (pinfunction "2_2") (pintype "passive"))
      (node (ref "X5") (pin "2") (pinfunction "2_2") (pintype "passive"))
      (node (ref "X6") (pin "4") (pinfunction "4_4") (pintype "passive"))
      (node (ref "X6") (pin "S1") (pinfunction "S_S1") (pintype "passive"))
      (node (ref "X6") (pin "S2") (pinfunction "S_S2") (pintype "passive"))
      (node (ref "X8") (pin "2") (pinfunction "2_2") (pintype "passive"))
      (node (ref "X9") (pin "2") (pinfunction "2_2") (pintype "passive"))
    )
    (net (code "14") (name "Net-(C7-Pad2)") (class "Default")
      (node (ref "C7") (pin "2") (pinfunction "2_2") (pintype "passive"))
      (node (ref "R15") (pin "2") (pinfunction "2_2") (pintype "passive"))
    )
    (net (code "15") (name "Net-(C11-Pad1)") (class "Default")
      (node (ref "C11") (pin "1") (pinfunction "1_1") (pintype "passive"))
      (node (ref "R22") (pin "1") (pinfunction "1_1") (pintype "passive"))
      (node (ref "R23") (pin "2") (pinfunction "2_2") (pintype "passive"))
    )
    (net (code "16") (name "Net-(C34-Pad2)") (class "Default")
      (node (ref "C34") (pin "2") (pinfunction "2_2") (pintype "passive"))
      (node (ref "R67") (pin "2") (pinfunction "2_2") (pintype "passive"))
    )
    (net (code "17") (name "Net-(C36-Pad1)") (class "Default")
      (node (ref "C36") (pin "1") (pinfunction "1_1") (pintype "passive"))
      (node (ref "R70") (pin "2") (pinfunction "2_2") (pintype "passive"))
      (node (ref "R71") (pin "1") (pinfunction "1_1") (pintype "passive"))
    )
    (net (code "18") (name "Net-(D2-PadA)") (class "Default")
      (node (ref "D2") (pin "A") (pinfunction "A_A") (pintype "passive"))
      (node (ref "R12") (pin "1") (pinfunction "1_1") (pintype "passive"))
      (node (ref "T1") (pin "E") (pinfunction "E_E") (pintype "passive"))
    )
    (net (code "19") (name "Net-(D4-PadA)") (class "Default")
      (node (ref "D4") (pin "A") (pinfunction "A_A") (pintype "passive"))
      (node (ref "Q1") (pin "E") (pinfunction "E_E") (pintype "passive"))
      (node (ref "R18") (pin "2") (pinfunction "2_2") (pintype "passive"))
      (node (ref "R20") (pin "1") (pinfunction "1_1") (pintype "passive"))
    )
    (net (code "20") (name "Net-(D5-C)") (class "Default")
      (node (ref "D5") (pin "3") (pinfunction "C_3") (pintype "passive"))
      (node (ref "D6") (pin "1") (pinfunction "A_1") (pintype "passive"))
    )
    (net (code "21") (name "Net-(D7-A)") (class "Default")
      (node (ref "D7") (pin "2") (pinfunction "A_2") (pintype "passive"))
      (node (ref "R34") (pin "2") (pinfunction "2_2") (pintype "passive"))
      (node (ref "R36") (pin "2") (pinfunction "2_2") (pintype "passive"))
    )
    (net (code "22") (name "Net-(D14-C)") (class "Default")
      (node (ref "D14") (pin "3") (pinfunction "C_3") (pintype "passive"))
      (node (ref "D15") (pin "1") (pinfunction "A_1") (pintype "passive"))
    )
    (net (code "23") (name "Net-(D16-PadA)") (class "Default")
      (node (ref "D16") (pin "A") (pinfunction "A_A") (pintype "passive"))
      (node (ref "R62") (pin "1") (pinfunction "1_1") (pintype "passive"))
      (node (ref "T6") (pin "E") (pinfunction "E_E") (pintype "passive"))
    )
    (net (code "24") (name "Net-(D18-PadA)") (class "Default")
      (node (ref "D18") (pin "A") (pinfunction "A_A") (pintype "passive"))
      (node (ref "Q3") (pin "E") (pinfunction "E_E") (pintype "passive"))
      (node (ref "R57") (pin "2") (pinfunction "2_2") (pintype "passive"))
      (node (ref "R68") (pin "1") (pinfunction "1_1") (pintype "passive"))
    )
    (net (code "25") (name "Net-(D19-A)") (class "Default")
      (node (ref "D19") (pin "2") (pinfunction "A_2") (pintype "passive"))
      (node (ref "R80") (pin "2") (pinfunction "2_2") (pintype "passive"))
      (node (ref "R82") (pin "2") (pinfunction "2_2") (pintype "passive"))
    )
    (net (code "26") (name "Net-(IC7A-I)") (class "Default")
      (node (ref "IC7") (pin "2") (pinfunction "I_2") (pintype "input"))
      (node (ref "IC9") (pin "1") (pinfunction "FOUT_1") (pintype "open_collector"))
      (node (ref "R19") (pin "1") (pinfunction "1_1") (pintype "passive"))
    )
    (net (code "27") (name "Net-(IC8-IN+)") (class "Default")
      (node (ref "C8") (pin "2") (pinfunction "2_2") (pintype "passive"))
      (node (ref "IC8") (pin "3") (pinfunction "IN+_3") (pintype "input"))
      (node (ref "R22") (pin "2") (pinfunction "2_2") (pintype "passive"))
    )
    (net (code "28") (name "Net-(IC8-IN-)") (class "Default")
      (node (ref "C10") (pin "1") (pinfunction "1_1") (pintype "passive"))
      (node (ref "IC8") (pin "2") (pinfunction "IN-_2") (pintype "input"))
      (node (ref "R26") (pin "2") (pinfunction "2_2") (pintype "passive"))
    )
    (net (code "29") (name "Net-(IC8-OUT)") (class "Default")
      (node (ref "C10") (pin "2") (pinfunction "2_2") (pintype "passive"))
      (node (ref "C11") (pin "2") (pinfunction "2_2") (pintype "passive"))
      (node (ref "IC8") (pin "6") (pinfunction "OUT_6") (pintype "output"))
      (node (ref "R26") (pin "1") (pinfunction "1_1") (pintype "passive"))
      (node (ref "R27") (pin "2") (pinfunction "2_2") (pintype "passive"))
      (node (ref "R28") (pin "1") (pinfunction "1_1") (pintype "passive"))
    )
    (net (code "30") (name "Net-(IC9-CT1)") (class "Default")
      (node (ref "C9") (pin "1") (pinfunction "1_1") (pintype "passive"))
      (node (ref "IC9") (pin "6") (pinfunction "CT1_6") (pintype "passive"))
    )
    (net (code "31") (name "Net-(IC9-CT2)") (class "Default")
      (node (ref "C9") (pin "2") (pinfunction "2_2") (pintype "passive"))
      (node (ref "IC9") (pin "7") (pinfunction "CT2_7") (pintype "passive"))
    )
    (net (code "32") (name "Net-(IC9-RT)") (class "Default")
      (node (ref "IC9") (pin "3") (pinfunction "RT_3") (pintype "passive"))
      (node (ref "R24") (pin "2") (pinfunction "2_2") (pintype "passive"))
    )
    (net (code "33") (name "Net-(IC15-IN-)") (class "Default")
      (node (ref "IC15") (pin "2") (pinfunction "IN-_2") (pintype "input"))
      (node (ref "R28") (pin "2") (pinfunction "2_2") (pintype "passive"))
      (node (ref "R29") (pin "2") (pinfunction "2_2") (pintype "passive"))
      (node (ref "R33") (pin "1") (pinfunction "1_1") (pintype "passive"))
    )
    (net (code "34") (name "Net-(IC15-OUT)") (class "Default")
      (node (ref "IC15") (pin "6") (pinfunction "OUT_6") (pintype "output"))
      (node (ref "R30") (pin "1") (pinfunction "1_1") (pintype "passive"))
      (node (ref "R33") (pin "2") (pinfunction "2_2") (pintype "passive"))
    )
    (net (code "35") (name "Net-(IC16-IN-)") (class "Default")
      (node (ref "IC16") (pin "2") (pinfunction "IN-_2") (pintype "input"))
      (node (ref "R30") (pin "2") (pinfunction "2_2") (pintype "passive"))
      (node (ref "R7") (pin "1") (pinfunction "A_1") (pintype "passive"))
      (node (ref "R7") (pin "2") (pinfunction "S_2") (pintype "passive"))
    )
    (net (code "36") (name "Net-(IC16-OUT)") (class "Default")
      (node (ref "IC16") (pin "6") (pinfunction "OUT_6") (pintype "output"))
      (node (ref "R31") (pin "2") (pinfunction "2_2") (pintype "passive"))
      (node (ref "R32") (pin "1") (pinfunction "1_1") (pintype "passive"))
    )
    (net (code "37") (name "Net-(IC17A-CLR)") (class "Default")
      (node (ref "IC17") (pin "1") (pinfunction "CLR_1") (pintype "input"))
      (node (ref "IC17") (pin "13") (pinfunction "CLR_13") (pintype "input"))
      (node (ref "IC4") (pin "4") (pinfunction "O_4") (pintype "output"))
    )
    (net (code "38") (name "Net-(IC17A-D)") (class "Default")
      (node (ref "IC17") (pin "10") (pinfunction "PRE_10") (pintype "input"))
      (node (ref "IC17") (pin "12") (pinfunction "D_12") (pintype "input"))
      (node (ref "IC17") (pin "2") (pinfunction "D_2") (pintype "input"))
      (node (ref "IC17") (pin "4") (pinfunction "PRE_4") (pintype "input"))
      (node (ref "R11") (pin "1") (pinfunction "1_1") (pintype "passive"))
    )
    (net (code "39") (name "Net-(IC17A-Q)") (class "Default")
      (node (ref "IC17") (pin "5") (pinfunction "Q_5") (pintype "output"))
      (node (ref "IC4") (pin "1") (pinfunction "I0_1") (pintype "input"))
      (node (ref "IC5") (pin "2") (pinfunction "I_2") (pintype "input"))
    )
    (net (code "40") (name "Net-(IC17B-Q)") (class "Default")
      (node (ref "IC17") (pin "9") (pinfunction "Q_9") (pintype "output"))
      (node (ref "IC4") (pin "2") (pinfunction "I1_2") (pintype "input"))
    )
    (net (code "41") (name "Net-(IC17B-~{Q})") (class "Default")
      (node (ref "IC17") (pin "8") (pinfunction "~{Q}_8") (pintype "output"))
      (node (ref "IC6") (pin "2") (pinfunction "I_2") (pintype "input"))
    )
    (net (code "42") (name "Net-(IC19-CT1)") (class "Default")
      (node (ref "C33") (pin "1") (pinfunction "1_1") (pintype "passive"))
      (node (ref "IC19") (pin "6") (pinfunction "CT1_6") (pintype "passive"))
    )
    (net (code "43") (name "Net-(IC19-CT2)") (class "Default")
      (node (ref "C33") (pin "2") (pinfunction "2_2") (pintype "passive"))
      (node (ref "IC19") (pin "7") (pinfunction "CT2_7") (pintype "passive"))
    )
    (net (code "44") (name "Net-(IC19-FOUT)") (class "Default")
      (node (ref "IC19") (pin "1") (pinfunction "FOUT_1") (pintype "open_collector"))
      (node (ref "IC23") (pin "2") (pinfunction "I_2") (pintype "input"))
      (node (ref "R59") (pin "1") (pinfunction "1_1") (pintype "passive"))
    )
    (net (code "45") (name "Net-(IC19-RT)") (class "Default")
      (node (ref "IC19") (pin "3") (pinfunction "RT_3") (pintype "passive"))
      (node (ref "R60") (pin "2") (pinfunction "2_2") (pintype "passive"))
    )
    (net (code "46") (name "Net-(IC20A-I0)") (class "Default")
      (node (ref "IC20") (pin "1") (pinfunction "I0_1") (pintype "input"))
      (node (ref "IC21") (pin "2") (pinfunction "I_2") (pintype "input"))
      (node (ref "IC25") (pin "5") (pinfunction "Q_5") (pintype "output"))
    )
    (net (code "47") (name "Net-(IC20A-I1)") (class "Default")
      (node (ref "IC20") (pin "2") (pinfunction "I1_2") (pintype "input"))
      (node (ref "IC25") (pin "9") (pinfunction "Q_9") (pintype "output"))
    )
    (net (code "48") (name "Net-(IC20A-O)") (class "Default")
      (node (ref "IC20") (pin "4") (pinfunction "O_4") (pintype "output"))
      (node (ref "IC25") (pin "1") (pinfunction "CLR_1") (pintype "input"))
      (node (ref "IC25") (pin "13") (pinfunction "CLR_13") (pintype "input"))
    )
    (net (code "49") (name "Net-(IC22A-I)") (class "Default")
      (node (ref "IC22") (pin "2") (pinfunction "I_2") (pintype "input"))
      (node (ref "IC25") (pin "8") (pinfunction "~{Q}_8") (pintype "output"))
    )
    (net (code "50") (name "Net-(IC24-IN+)") (class "Default")
      (node (ref "C37") (pin "2") (pinfunction "2_2") (pintype "passive"))
      (node (ref "IC24") (pin "3") (pinfunction "IN+_3") (pintype "input"))
      (node (ref "R71") (pin "2") (pinfunction "2_2") (pintype "passive"))
    )
    (net (code "51") (name "Net-(IC24-IN-)") (class "Default")
      (node (ref "C35") (pin "1") (pinfunction "1_1") (pintype "passive"))
      (node (ref "IC24") (pin "2") (pinfunction "IN-_2") (pintype "input"))
      (node (ref "R72") (pin "2") (pinfunction "2_2") (pintype "passive"))
    )
    (net (code "52") (name "Net-(IC24-OUT)") (class "Default")
      (node (ref "C35") (pin "2") (pinfunction "2_2") (pintype "passive"))
      (node (ref "C36") (pin "2") (pinfunction "2_2") (pintype "passive"))
      (node (ref "IC24") (pin "6") (pinfunction "OUT_6") (pintype "output"))
      (node (ref "R72") (pin "1") (pinfunction "1_1") (pintype "passive"))
      (node (ref "R73") (pin "2") (pinfunction "2_2") (pintype "passive"))
      (node (ref "R74") (pin "1") (pinfunction "1_1") (pintype "passive"))
    )
    (net (code "53") (name "Net-(IC25A-D)") (class "Default")
      (node (ref "IC25") (pin "10") (pinfunction "PRE_10") (pintype "input"))
      (node (ref "IC25") (pin "12") (pinfunction "D_12") (pintype "input"))
      (node (ref "IC25") (pin "2") (pinfunction "D_2") (pintype "input"))
      (node (ref "IC25") (pin "4") (pinfunction "PRE_4") (pintype "input"))
      (node (ref "R58") (pin "1") (pinfunction "1_1") (pintype "passive"))
    )
    (net (code "54") (name "Net-(IC26-IN-)") (class "Default")
      (node (ref "IC26") (pin "2") (pinfunction "IN-_2") (pintype "input"))
      (node (ref "R74") (pin "2") (pinfunction "2_2") (pintype "passive"))
      (node (ref "R75") (pin "2") (pinfunction "2_2") (pintype "passive"))
      (node (ref "R79") (pin "1") (pinfunction "1_1") (pintype "passive"))
    )
    (net (code "55") (name "Net-(IC26-OUT)") (class "Default")
      (node (ref "IC26") (pin "6") (pinfunction "OUT_6") (pintype "output"))
      (node (ref "R76") (pin "1") (pinfunction "1_1") (pintype "passive"))
      (node (ref "R79") (pin "2") (pinfunction "2_2") (pintype "passive"))
    )
    (net (code "56") (name "Net-(IC27-IN-)") (class "Default")
      (node (ref "IC27") (pin "2") (pinfunction "IN-_2") (pintype "input"))
      (node (ref "R76") (pin "2") (pinfunction "2_2") (pintype "passive"))
      (node (ref "R83") (pin "1") (pinfunction "A_1") (pintype "passive"))
      (node (ref "R83") (pin "2") (pinfunction "S_2") (pintype "passive"))
    )
    (net (code "57") (name "Net-(IC27-OUT)") (class "Default")
      (node (ref "IC27") (pin "6") (pinfunction "OUT_6") (pintype "output"))
      (node (ref "R77") (pin "2") (pinfunction "2_2") (pintype "passive"))
      (node (ref "R78") (pin "1") (pinfunction "1_1") (pintype "passive"))
    )
    (net (code "58") (name "Net-(LED1-PadC)") (class "Default")
      (node (ref "LED1") (pin "C") (pinfunction "C_C") (pintype "passive"))
      (node (ref "R14") (pin "2") (pinfunction "2_2") (pintype "passive"))
      (node (ref "T1") (pin "B") (pinfunction "B_B") (pintype "passive"))
    )
    (net (code "59") (name "Net-(LED5-PadC)") (class "Default")
      (node (ref "LED5") (pin "C") (pinfunction "C_C") (pintype "passive"))
      (node (ref "R66") (pin "2") (pinfunction "2_2") (pintype "passive"))
      (node (ref "T6") (pin "B") (pinfunction "B_B") (pintype "passive"))
    )
    (net (code "60") (name "Net-(Q1-PadB)") (class "Default")
      (node (ref "Q1") (pin "B") (pinfunction "B_B") (pintype "passive"))
      (node (ref "R16") (pin "2") (pinfunction "2_2") (pintype "passive"))
    )
    (net (code "61") (name "Net-(Q1-PadC)") (class "Default")
      (node (ref "Q1") (pin "C") (pinfunction "C_C") (pintype "passive"))
      (node (ref "R17") (pin "1") (pinfunction "1_1") (pintype "passive"))
    )
    (net (code "62") (name "Net-(Q3-PadB)") (class "Default")
      (node (ref "Q3") (pin "B") (pinfunction "B_B") (pintype "passive"))
      (node (ref "R63") (pin "2") (pinfunction "2_2") (pintype "passive"))
    )
    (net (code "63") (name "Net-(Q3-PadC)") (class "Default")
      (node (ref "Q3") (pin "C") (pinfunction "C_C") (pintype "passive"))
      (node (ref "R64") (pin "1") (pinfunction "1_1") (pintype "passive"))
    )
    (net (code "64") (name "Net-(R1-Pad1)") (class "Default")
      (node (ref "R1") (pin "1") (pinfunction "1_1") (pintype "passive"))
      (node (ref "X5") (pin "1") (pinfunction "1_1") (pintype "passive"))
    )
    (net (code "65") (name "Net-(R7-E)") (class "Default")
      (node (ref "R31") (pin "1") (pinfunction "1_1") (pintype "passive"))
      (node (ref "R7") (pin "3") (pinfunction "E_3") (pintype "passive"))
    )
    (net (code "66") (name "Net-(R25-E)") (class "Default")
      (node (ref "R24") (pin "1") (pinfunction "1_1") (pintype "passive"))
      (node (ref "R25") (pin "3") (pinfunction "E_3") (pintype "passive"))
    )
    (net (code "67") (name "Net-(R32-Pad2)") (class "Default")
      (node (ref "R32") (pin "2") (pinfunction "2_2") (pintype "passive"))
      (node (ref "X4") (pin "1") (pinfunction "1_1") (pintype "passive"))
    )
    (net (code "68") (name "Net-(R35-E)") (class "Default")
      (node (ref "R35") (pin "3") (pinfunction "E_3") (pintype "passive"))
      (node (ref "R36") (pin "1") (pinfunction "1_1") (pintype "passive"))
    )
    (net (code "69") (name "Net-(R35-S)") (class "Default")
      (node (ref "R29") (pin "1") (pinfunction "1_1") (pintype "passive"))
      (node (ref "R35") (pin "2") (pinfunction "S_2") (pintype "passive"))
    )
    (net (code "70") (name "Net-(R61-E)") (class "Default")
      (node (ref "R60") (pin "1") (pinfunction "1_1") (pintype "passive"))
      (node (ref "R61") (pin "3") (pinfunction "E_3") (pintype "passive"))
    )
    (net (code "71") (name "Net-(R78-Pad2)") (class "Default")
      (node (ref "R78") (pin "2") (pinfunction "2_2") (pintype "passive"))
      (node (ref "X8") (pin "1") (pinfunction "1_1") (pintype "passive"))
    )
    (net (code "72") (name "Net-(R81-E)") (class "Default")
      (node (ref "R81") (pin "3") (pinfunction "E_3") (pintype "passive"))
      (node (ref "R82") (pin "1") (pinfunction "1_1") (pintype "passive"))
    )
    (net (code "73") (name "Net-(R81-S)") (class "Default")
      (node (ref "R75") (pin "1") (pinfunction "1_1") (pintype "passive"))
      (node (ref "R81") (pin "2") (pinfunction "S_2") (pintype "passive"))
    )
    (net (code "74") (name "Net-(R83-E)") (class "Default")
      (node (ref "R77") (pin "1") (pinfunction "1_1") (pintype "passive"))
      (node (ref "R83") (pin "3") (pinfunction "E_3") (pintype "passive"))
    )
    (net (code "75") (name "Net-(R84-Pad1)") (class "Default")
      (node (ref "R84") (pin "1") (pinfunction "1_1") (pintype "passive"))
      (node (ref "X9") (pin "1") (pinfunction "1_1") (pintype "passive"))
    )
    (net (code "76") (name "Net-(T2-B)") (class "Default")
      (node (ref "LED2") (pin "A") (pinfunction "A_A") (pintype "passive"))
      (node (ref "R14") (pin "1") (pinfunction "1_1") (pintype "passive"))
      (node (ref "T2") (pin "1") (pinfunction "B_1") (pintype "passive"))
    )
    (net (code "77") (name "Net-(T2-C)") (class "Default")
      (node (ref "C7") (pin "1") (pinfunction "1_1") (pintype "passive"))
      (node (ref "R16") (pin "1") (pinfunction "1_1") (pintype "passive"))
      (node (ref "T1") (pin "C") (pinfunction "C_C") (pintype "passive"))
      (node (ref "T2") (pin "3") (pinfunction "C_3") (pintype "passive"))
    )
    (net (code "78") (name "Net-(T2-E)") (class "Default")
      (node (ref "D3") (pin "C") (pinfunction "C_C") (pintype "passive"))
      (node (ref "R13") (pin "2") (pinfunction "2_2") (pintype "passive"))
      (node (ref "T2") (pin "2") (pinfunction "E_2") (pintype "passive"))
    )
    (net (code "79") (name "Net-(T5-B)") (class "Default")
      (node (ref "LED6") (pin "A") (pinfunction "A_A") (pintype "passive"))
      (node (ref "R66") (pin "1") (pinfunction "1_1") (pintype "passive"))
      (node (ref "T5") (pin "1") (pinfunction "B_1") (pintype "passive"))
    )
    (net (code "80") (name "Net-(T5-C)") (class "Default")
      (node (ref "C34") (pin "1") (pinfunction "1_1") (pintype "passive"))
      (node (ref "R63") (pin "1") (pinfunction "1_1") (pintype "passive"))
      (node (ref "T5") (pin "3") (pinfunction "C_3") (pintype "passive"))
      (node (ref "T6") (pin "C") (pinfunction "C_C") (pintype "passive"))
    )
    (net (code "81") (name "Net-(T5-E)") (class "Default")
      (node (ref "D17") (pin "C") (pinfunction "C_C") (pintype "passive"))
      (node (ref "R65") (pin "2") (pinfunction "2_2") (pintype "passive"))
      (node (ref "T5") (pin "2") (pinfunction "E_2") (pintype "passive"))
    )
    (net (code "82") (name "PLL_OUT") (class "Default")
      (node (ref "IC17") (pin "3") (pinfunction "CLK_3") (pintype "input"))
      (node (ref "IC7") (pin "4") (pinfunction "O_4") (pintype "output"))
    )
    (net (code "83") (name "PLL_OUT2") (class "Default")
      (node (ref "IC23") (pin "4") (pinfunction "O_4") (pintype "output"))
      (node (ref "IC25") (pin "3") (pinfunction "CLK_3") (pintype "input"))
    )
    (net (code "84") (name "unconnected-(IC17A-~{Q}-Pad6)") (class "Default")
      (node (ref "IC17") (pin "6") (pinfunction "~{Q}_6") (pintype "output"))
    )
    (net (code "85") (name "unconnected-(IC25A-~{Q}-Pad6)") (class "Default")
      (node (ref "IC25") (pin "6") (pinfunction "~{Q}_6") (pintype "output"))
    )
    (net (code "86") (name "unconnected-(X2A-2-PadA2)") (class "Default")
      (node (ref "X2") (pin "A2") (pinfunction "2_A2") (pintype "passive"))
    )
    (net (code "87") (name "unconnected-(X2A-3-PadA3)") (class "Default")
      (node (ref "X2") (pin "A3") (pinfunction "3_A3") (pintype "passive"))
    )
    (net (code "88") (name "unconnected-(X2A-4-PadA4)") (class "Default")
      (node (ref "X2") (pin "A4") (pinfunction "4_A4") (pintype "passive"))
    )
    (net (code "89") (name "unconnected-(X2A-5-PadA5)") (class "Default")
      (node (ref "X2") (pin "A5") (pinfunction "5_A5") (pintype "passive"))
    )
    (net (code "90") (name "unconnected-(X2A-6-PadA6)") (class "Default")
      (node (ref "X2") (pin "A6") (pinfunction "6_A6") (pintype "passive"))
    )
    (net (code "91") (name "unconnected-(X2A-7-PadA7)") (class "Default")
      (node (ref "X2") (pin "A7") (pinfunction "7_A7") (pintype "passive"))
    )
    (net (code "92") (name "unconnected-(X2A-8-PadA8)") (class "Default")
      (node (ref "X2") (pin "A8") (pinfunction "8_A8") (pintype "passive"))
    )
    (net (code "93") (name "unconnected-(X2A-9-PadA9)") (class "Default")
      (node (ref "X2") (pin "A9") (pinfunction "9_A9") (pintype "passive"))
    )
    (net (code "94") (name "unconnected-(X2A-11-PadA11)") (class "Default")
      (node (ref "X2") (pin "A11") (pinfunction "11_A11") (pintype "passive"))
    )
    (net (code "95") (name "unconnected-(X2A-12-PadA12)") (class "Default")
      (node (ref "X2") (pin "A12") (pinfunction "12_A12") (pintype "passive"))
    )
    (net (code "96") (name "unconnected-(X2A-13-PadA13)") (class "Default")
      (node (ref "X2") (pin "A13") (pinfunction "13_A13") (pintype "passive"))
    )
    (net (code "97") (name "unconnected-(X2A-14-PadA14)") (class "Default")
      (node (ref "X2") (pin "A14") (pinfunction "14_A14") (pintype "passive"))
    )
    (net (code "98") (name "unconnected-(X2A-15-PadA15)") (class "Default")
      (node (ref "X2") (pin "A15") (pinfunction "15_A15") (pintype "passive"))
    )
    (net (code "99") (name "unconnected-(X2A-16-PadA16)") (class "Default")
      (node (ref "X2") (pin "A16") (pinfunction "16_A16") (pintype "passive"))
    )
    (net (code "100") (name "unconnected-(X2A-18-PadA18)") (class "Default")
      (node (ref "X2") (pin "A18") (pinfunction "18_A18") (pintype "passive"))
    )
    (net (code "101") (name "unconnected-(X2A-19-PadA19)") (class "Default")
      (node (ref "X2") (pin "A19") (pinfunction "19_A19") (pintype "passive"))
    )
    (net (code "102") (name "unconnected-(X2A-20-PadA20)") (class "Default")
      (node (ref "X2") (pin "A20") (pinfunction "20_A20") (pintype "passive"))
    )
    (net (code "103") (name "unconnected-(X2A-21-PadA21)") (class "Default")
      (node (ref "X2") (pin "A21") (pinfunction "21_A21") (pintype "passive"))
    )
    (net (code "104") (name "unconnected-(X2A-22-PadA22)") (class "Default")
      (node (ref "X2") (pin "A22") (pinfunction "22_A22") (pintype "passive"))
    )
    (net (code "105") (name "unconnected-(X2A-23-PadA23)") (class "Default")
      (node (ref "X2") (pin "A23") (pinfunction "23_A23") (pintype "passive"))
    )
    (net (code "106") (name "unconnected-(X2A-24-PadA24)") (class "Default")
      (node (ref "X2") (pin "A24") (pinfunction "24_A24") (pintype "passive"))
    )
    (net (code "107") (name "unconnected-(X2A-25-PadA25)") (class "Default")
      (node (ref "X2") (pin "A25") (pinfunction "25_A25") (pintype "passive"))
    )
    (net (code "108") (name "unconnected-(X2A-26-PadA26)") (class "Default")
      (node (ref "X2") (pin "A26") (pinfunction "26_A26") (pintype "passive"))
    )
    (net (code "109") (name "unconnected-(X2A-27-PadA27)") (class "Default")
      (node (ref "X2") (pin "A27") (pinfunction "27_A27") (pintype "passive"))
    )
    (net (code "110") (name "unconnected-(X2A-28-PadA28)") (class "Default")
      (node (ref "X2") (pin "A28") (pinfunction "28_A28") (pintype "passive"))
    )
    (net (code "111") (name "unconnected-(X2A-29-PadA29)") (class "Default")
      (node (ref "X2") (pin "A29") (pinfunction "29_A29") (pintype "passive"))
    )
    (net (code "112") (name "unconnected-(X2A-30-PadA30)") (class "Default")
      (node (ref "X2") (pin "A30") (pinfunction "30_A30") (pintype "passive"))
    )
    (net (code "113") (name "unconnected-(X2A-31-PadA31)") (class "Default")
      (node (ref "X2") (pin "A31") (pinfunction "31_A31") (pintype "passive"))
    )
    (net (code "114") (name "unconnected-(X2B-2-PadB2)") (class "Default")
      (node (ref "X2") (pin "B2") (pinfunction "2_B2") (pintype "passive"))
    )
    (net (code "115") (name "unconnected-(X2B-3-PadB3)") (class "Default")
      (node (ref "X2") (pin "B3") (pinfunction "3_B3") (pintype "passive"))
    )
    (net (code "116") (name "unconnected-(X2B-4-PadB4)") (class "Default")
      (node (ref "X2") (pin "B4") (pinfunction "4_B4") (pintype "passive"))
    )
    (net (code "117") (name "unconnected-(X2B-5-PadB5)") (class "Default")
      (node (ref "X2") (pin "B5") (pinfunction "5_B5") (pintype "passive"))
    )
    (net (code "118") (name "unconnected-(X2B-6-PadB6)") (class "Default")
      (node (ref "X2") (pin "B6") (pinfunction "6_B6") (pintype "passive"))
    )
    (net (code "119") (name "unconnected-(X2B-7-PadB7)") (class "Default")
      (node (ref "X2") (pin "B7") (pinfunction "7_B7") (pintype "passive"))
    )
    (net (code "120") (name "unconnected-(X2B-8-PadB8)") (class "Default")
      (node (ref "X2") (pin "B8") (pinfunction "8_B8") (pintype "passive"))
    )
    (net (code "121") (name "unconnected-(X2B-9-PadB9)") (class "Default")
      (node (ref "X2") (pin "B9") (pinfunction "9_B9") (pintype "passive"))
    )
    (net (code "122") (name "unconnected-(X2B-11-PadB11)") (class "Default")
      (node (ref "X2") (pin "B11") (pinfunction "11_B11") (pintype "passive"))
    )
    (net (code "123") (name "unconnected-(X2B-12-PadB12)") (class "Default")
      (node (ref "X2") (pin "B12") (pinfunction "12_B12") (pintype "passive"))
    )
    (net (code "124") (name "unconnected-(X2B-13-PadB13)") (class "Default")
      (node (ref "X2") (pin "B13") (pinfunction "13_B13") (pintype "passive"))
    )
    (net (code "125") (name "unconnected-(X2B-14-PadB14)") (class "Default")
      (node (ref "X2") (pin "B14") (pinfunction "14_B14") (pintype "passive"))
    )
    (net (code "126") (name "unconnected-(X2B-15-PadB15)") (class "Default")
      (node (ref "X2") (pin "B15") (pinfunction "15_B15") (pintype "passive"))
    )
    (net (code "127") (name "unconnected-(X2B-16-PadB16)") (class "Default")
      (node (ref "X2") (pin "B16") (pinfunction "16_B16") (pintype "passive"))
    )
    (net (code "128") (name "unconnected-(X2B-18-PadB18)") (class "Default")
      (node (ref "X2") (pin "B18") (pinfunction "18_B18") (pintype "passive"))
    )
    (net (code "129") (name "unconnected-(X2B-19-PadB19)") (class "Default")
      (node (ref "X2") (pin "B19") (pinfunction "19_B19") (pintype "passive"))
    )
    (net (code "130") (name "unconnected-(X2B-20-PadB20)") (class "Default")
      (node (ref "X2") (pin "B20") (pinfunction "20_B20") (pintype "passive"))
    )
    (net (code "131") (name "unconnected-(X2B-21-PadB21)") (class "Default")
      (node (ref "X2") (pin "B21") (pinfunction "21_B21") (pintype "passive"))
    )
    (net (code "132") (name "unconnected-(X2B-22-PadB22)") (class "Default")
      (node (ref "X2") (pin "B22") (pinfunction "22_B22") (pintype "passive"))
    )
    (net (code "133") (name "unconnected-(X2B-23-PadB23)") (class "Default")
      (node (ref "X2") (pin "B23") (pinfunction "23_B23") (pintype "passive"))
    )
    (net (code "134") (name "unconnected-(X2B-24-PadB24)") (class "Default")
      (node (ref "X2") (pin "B24") (pinfunction "24_B24") (pintype "passive"))
    )
    (net (code "135") (name "unconnected-(X2B-25-PadB25)") (class "Default")
      (node (ref "X2") (pin "B25") (pinfunction "25_B25") (pintype "passive"))
    )
    (net (code "136") (name "unconnected-(X2B-26-PadB26)") (class "Default")
      (node (ref "X2") (pin "B26") (pinfunction "26_B26") (pintype "passive"))
    )
    (net (code "137") (name "unconnected-(X2B-27-PadB27)") (class "Default")
      (node (ref "X2") (pin "B27") (pinfunction "27_B27") (pintype "passive"))
    )
    (net (code "138") (name "unconnected-(X2B-28-PadB28)") (class "Default")
      (node (ref "X2") (pin "B28") (pinfunction "28_B28") (pintype "passive"))
    )
    (net (code "139") (name "unconnected-(X2B-29-PadB29)") (class "Default")
      (node (ref "X2") (pin "B29") (pinfunction "29_B29") (pintype "passive"))
    )
    (net (code "140") (name "unconnected-(X2B-30-PadB30)") (class "Default")
      (node (ref "X2") (pin "B30") (pinfunction "30_B30") (pintype "passive"))
    )
    (net (code "141") (name "unconnected-(X2B-31-PadB31)") (class "Default")
      (node (ref "X2") (pin "B31") (pinfunction "31_B31") (pintype "passive"))
    )
  )
)
